# DC_Engine_and_Servo_Engine.net
KiCad netlist of a schematic drawn in Altium Designer
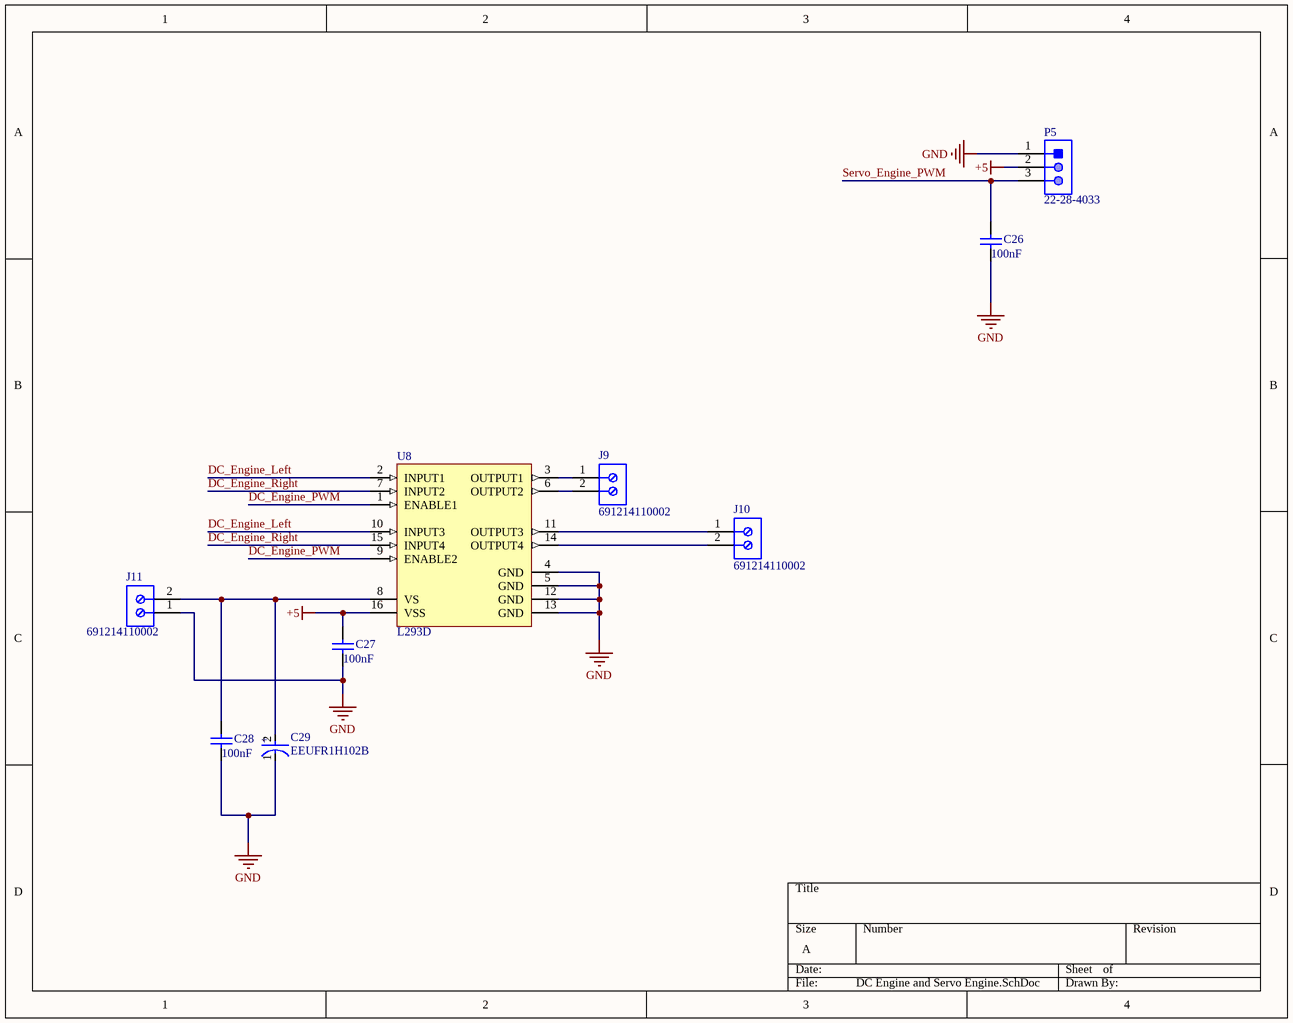
[diagram p0: DC Engine and Servo Engine.SchDoc]

(export (version "E")
  (design (tool "Eeschema 10.0.6"))
  (components
    (comp (ref "C26")
      (value "100nF")
      (footprint "CAPC2013X135X45LL10T25")
      (fields (field (name "MANUFACTURER") "Murata") (field (name "PART NUMBER") "GRM21BR71H105KA12L"))
      (libsource (lib "Altium Content Vault") (part "CAP"))
    )
    (comp (ref "C27")
      (value "100nF")
      (footprint "CAPC2013X135X45LL10T25")
      (fields (field (name "MANUFACTURER") "Murata") (field (name "PART NUMBER") "GRM21BR71H105KA12L"))
      (libsource (lib "Altium Content Vault") (part "CAP"))
    )
    (comp (ref "C28")
      (value "100nF")
      (footprint "CAPC2013X135X45LL10T25")
      (fields (field (name "MANUFACTURER") "Murata") (field (name "PART NUMBER") "GRM21BR71H105KA12L"))
      (libsource (lib "Altium Content Vault") (part "CAP"))
    )
    (comp (ref "C29")
      (value "EEUFR1H102B")
      (footprint "FP-RAD-TH-D_16_0_5-L_25_2-MFG")
      (description "Aluminum Electrolytic Capacitors (Radial Lead Type) 1000uF ±20% 50V")
      (fields (field (name "TOLERANCE") "20%"))
      (libsource (lib "Altium Content Vault") (part "203bc49f2ac43e59fd269a8c329ed05"))
    )
    (comp (ref "J9")
      (value "691214110002")
      (footprint "691214110002")
      (description "Serie 2141 - 3.50 mm Horizontal Entry Modular with Rising Cage Clamp WR-TBL, 2 pin")
      (fields (field (name "MANUFACTURER") "Wurth Elektronik") (field (name "PUBLISHER") "WurthElektronik"))
      (libsource (lib "Altium Content Vault") (part "WE-CN-1P-F-TB2"))
    )
    (comp (ref "J10")
      (value "691214110002")
      (footprint "691214110002")
      (description "Serie 2141 - 3.50 mm Horizontal Entry Modular with Rising Cage Clamp WR-TBL, 2 pin")
      (fields (field (name "MANUFACTURER") "Wurth Elektronik") (field (name "PUBLISHER") "WurthElektronik"))
      (libsource (lib "Altium Content Vault") (part "WE-CN-1P-F-TB2"))
    )
    (comp (ref "J11")
      (value "691214110002")
      (footprint "691214110002")
      (description "Serie 2141 - 3.50 mm Horizontal Entry Modular with Rising Cage Clamp WR-TBL, 2 pin")
      (fields (field (name "MANUFACTURER") "Wurth Elektronik") (field (name "PUBLISHER") "WurthElektronik"))
      (libsource (lib "Altium Content Vault") (part "WE-CN-1P-F-TB2"))
    )
    (comp (ref "P5")
      (value "22-28-4033")
      (footprint "MOLX-22-28-4033_V")
      (description "Male Header, Pitch 2.54 mm, 1 x 3 Position, Height 8.38 mm, Tail Length 3.18 mm, RoHS, Bulk")
      (fields (field (name "MANUFACTURER") "Molex"))
      (libsource (lib "Altium Content Vault") (part "CN-1P-M-R3"))
    )
    (comp (ref "U8")
      (value "L293D")
      (footprint "STM-L293D-16")
      (description "Push-Pull Four Channel Driver with Diode, 4.5 to 36 V, -40 to 150 degC, 16-Pin PDIP, RoHS, Tube")
      (fields (field (name "MANUFACTURER") "STMicroelectronics"))
      (libsource (lib "Altium Content Vault") (part "STM-L293D-16"))
    )
  )
  (nets
    (net (code "1") (name "+5") (class "Default")
      (node (ref "C27") (pin "2") (pinfunction "2_2") (pintype "passive"))
      (node (ref "P5") (pin "2") (pinfunction "2_2") (pintype "passive"))
      (node (ref "U8") (pin "16") (pinfunction "VSS_16") (pintype "power_in"))
    )
    (net (code "2") (name "/DC_Engine_Left") (class "Default")
      (node (ref "U8") (pin "10") (pinfunction "INPUT3_10") (pintype "input"))
      (node (ref "U8") (pin "2") (pinfunction "INPUT1_2") (pintype "input"))
    )
    (net (code "3") (name "/DC_Engine_PWM") (class "Default")
      (node (ref "U8") (pin "1") (pinfunction "ENABLE1_1") (pintype "input"))
      (node (ref "U8") (pin "9") (pinfunction "ENABLE2_9") (pintype "input"))
    )
    (net (code "4") (name "/DC_Engine_Right") (class "Default")
      (node (ref "U8") (pin "15") (pinfunction "INPUT4_15") (pintype "input"))
      (node (ref "U8") (pin "7") (pinfunction "INPUT2_7") (pintype "input"))
    )
    (net (code "5") (name "/Servo_Engine_PWM") (class "Default")
      (node (ref "C26") (pin "2") (pinfunction "2_2") (pintype "passive"))
      (node (ref "P5") (pin "3") (pinfunction "3_3") (pintype "passive"))
    )
    (net (code "6") (name "GND") (class "Default")
      (node (ref "C26") (pin "1") (pinfunction "1_1") (pintype "passive"))
      (node (ref "C27") (pin "1") (pinfunction "1_1") (pintype "passive"))
      (node (ref "C28") (pin "1") (pinfunction "1_1") (pintype "passive"))
      (node (ref "C29") (pin "1") (pinfunction "C_1") (pintype "passive"))
      (node (ref "J11") (pin "1") (pinfunction "1_1") (pintype "passive"))
      (node (ref "P5") (pin "1") (pinfunction "1_1") (pintype "passive"))
      (node (ref "U8") (pin "12") (pinfunction "GND_12") (pintype "power_in"))
      (node (ref "U8") (pin "13") (pinfunction "GND_13") (pintype "power_in"))
      (node (ref "U8") (pin "4") (pinfunction "GND_4") (pintype "power_in"))
      (node (ref "U8") (pin "5") (pinfunction "GND_5") (pintype "power_in"))
    )
    (net (code "7") (name "Net-(C29-A)") (class "Default")
      (node (ref "C28") (pin "2") (pinfunction "2_2") (pintype "passive"))
      (node (ref "C29") (pin "2") (pinfunction "A_2") (pintype "passive"))
      (node (ref "J11") (pin "2") (pinfunction "2_2") (pintype "passive"))
      (node (ref "U8") (pin "8") (pinfunction "VS_8") (pintype "power_in"))
    )
    (net (code "8") (name "Net-(U8-OUTPUT1)") (class "Default")
      (node (ref "J9") (pin "1") (pinfunction "1_1") (pintype "passive"))
      (node (ref "U8") (pin "3") (pinfunction "OUTPUT1_3") (pintype "output"))
    )
    (net (code "9") (name "Net-(U8-OUTPUT2)") (class "Default")
      (node (ref "J9") (pin "2") (pinfunction "2_2") (pintype "passive"))
      (node (ref "U8") (pin "6") (pinfunction "OUTPUT2_6") (pintype "output"))
    )
    (net (code "10") (name "Net-(U8-OUTPUT3)") (class "Default")
      (node (ref "J10") (pin "1") (pinfunction "1_1") (pintype "passive"))
      (node (ref "U8") (pin "11") (pinfunction "OUTPUT3_11") (pintype "output"))
    )
    (net (code "11") (name "Net-(U8-OUTPUT4)") (class "Default")
      (node (ref "J10") (pin "2") (pinfunction "2_2") (pintype "passive"))
      (node (ref "U8") (pin "14") (pinfunction "OUTPUT4_14") (pintype "output"))
    )
  )
)
